# TPS65273V-Board.net
KiCad netlist of a schematic drawn in EAGLE
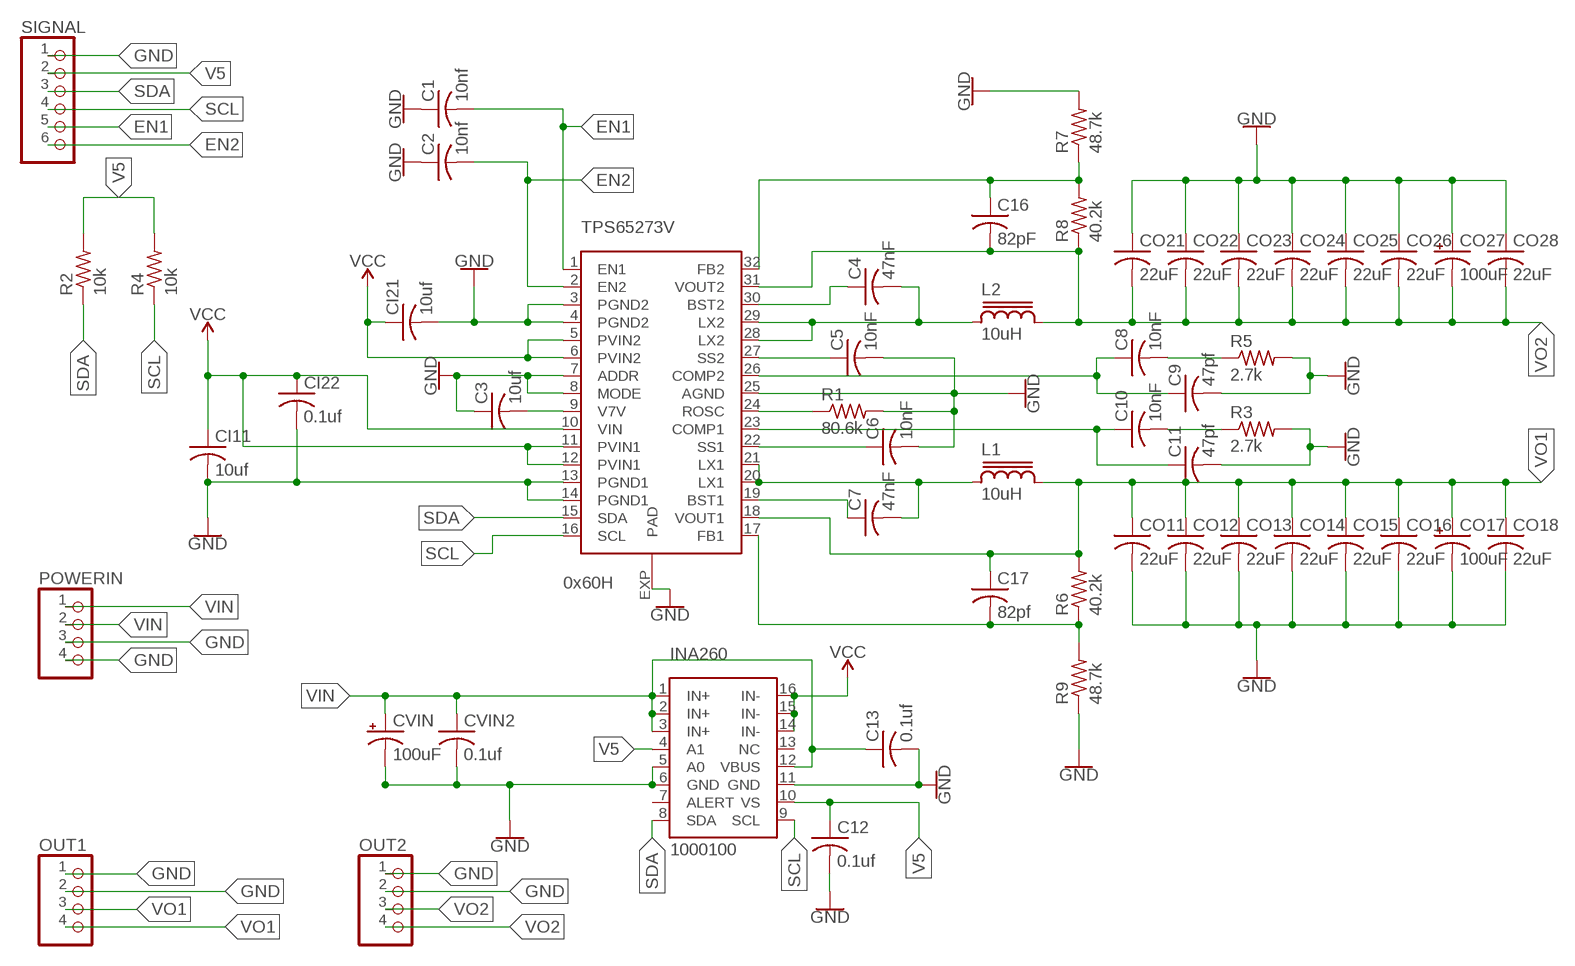
[diagram p0: schematic, sheet 1]

(export (version "E")
  (design (tool "Eeschema 10.0.6"))
  (components
    (comp (ref "C1")
      (value "10nf")
      (footprint "eagle-import:C0805")
      (libsource (lib "eagle-import") (part "C-USC0805"))
    )
    (comp (ref "C2")
      (value "10nf")
      (footprint "eagle-import:C0805")
      (libsource (lib "eagle-import") (part "C-USC0805"))
    )
    (comp (ref "C3")
      (value "10uf")
      (footprint "eagle-import:C0805")
      (libsource (lib "eagle-import") (part "C-USC0805"))
    )
    (comp (ref "C4")
      (value "47nF")
      (footprint "eagle-import:C0805")
      (libsource (lib "eagle-import") (part "C-USC0805"))
    )
    (comp (ref "C5")
      (value "10nF")
      (footprint "eagle-import:C0805")
      (libsource (lib "eagle-import") (part "C-USC0805"))
    )
    (comp (ref "C6")
      (value "10nF")
      (footprint "eagle-import:C0805")
      (libsource (lib "eagle-import") (part "C-USC0805"))
    )
    (comp (ref "C7")
      (value "47nF")
      (footprint "eagle-import:C0805")
      (libsource (lib "eagle-import") (part "C-USC0805"))
    )
    (comp (ref "C8")
      (value "10nF")
      (footprint "eagle-import:C0805")
      (libsource (lib "eagle-import") (part "C-USC0805"))
    )
    (comp (ref "C9")
      (value "47pf")
      (footprint "eagle-import:C0805")
      (libsource (lib "eagle-import") (part "C-USC0805"))
    )
    (comp (ref "C10")
      (value "10nF")
      (footprint "eagle-import:C0805")
      (libsource (lib "eagle-import") (part "C-USC0805"))
    )
    (comp (ref "C11")
      (value "47pf")
      (footprint "eagle-import:C0805")
      (libsource (lib "eagle-import") (part "C-USC0805"))
    )
    (comp (ref "C12")
      (value "0.1uf")
      (footprint "eagle-import:C0805")
      (libsource (lib "eagle-import") (part "C-USC0805"))
    )
    (comp (ref "C13")
      (value "0.1uf")
      (footprint "eagle-import:C0805")
      (libsource (lib "eagle-import") (part "C-USC0805"))
    )
    (comp (ref "C16")
      (value "82pF")
      (footprint "eagle-import:C0805")
      (libsource (lib "eagle-import") (part "C-USC0805"))
    )
    (comp (ref "C17")
      (value "82pf")
      (footprint "eagle-import:C0805")
      (libsource (lib "eagle-import") (part "C-USC0805"))
    )
    (comp (ref "CI11")
      (value "10uf")
      (footprint "eagle-import:C1210")
      (libsource (lib "eagle-import") (part "C-USC1210"))
    )
    (comp (ref "CI21")
      (value "10uf")
      (footprint "eagle-import:C1210")
      (libsource (lib "eagle-import") (part "C-USC1210"))
    )
    (comp (ref "CI22")
      (value "0.1uf")
      (footprint "eagle-import:C0805")
      (libsource (lib "eagle-import") (part "C-USC0805"))
    )
    (comp (ref "CO11")
      (value "22uF")
      (footprint "eagle-import:C0805")
      (libsource (lib "eagle-import") (part "C-USC0805"))
    )
    (comp (ref "CO12")
      (value "22uF")
      (footprint "eagle-import:C0805")
      (libsource (lib "eagle-import") (part "C-USC0805"))
    )
    (comp (ref "CO13")
      (value "22uF")
      (footprint "eagle-import:C0805")
      (libsource (lib "eagle-import") (part "C-USC0805"))
    )
    (comp (ref "CO14")
      (value "22uF")
      (footprint "eagle-import:C0805")
      (libsource (lib "eagle-import") (part "C-USC0805"))
    )
    (comp (ref "CO15")
      (value "22uF")
      (footprint "eagle-import:C0805")
      (libsource (lib "eagle-import") (part "C-USC0805"))
    )
    (comp (ref "CO16")
      (value "22uF")
      (footprint "eagle-import:C0805")
      (libsource (lib "eagle-import") (part "C-USC0805"))
    )
    (comp (ref "CO17")
      (value "100uF")
      (footprint "eagle-import:PANASONIC_D")
      (libsource (lib "eagle-import") (part "100UF-POLAR-25V-20%(ELEC)"))
    )
    (comp (ref "CO18")
      (value "22uF")
      (footprint "eagle-import:C0805")
      (libsource (lib "eagle-import") (part "C-USC0805"))
    )
    (comp (ref "CO21")
      (value "22uF")
      (footprint "eagle-import:C0805")
      (libsource (lib "eagle-import") (part "C-USC0805"))
    )
    (comp (ref "CO22")
      (value "22uF")
      (footprint "eagle-import:C0805")
      (libsource (lib "eagle-import") (part "C-USC0805"))
    )
    (comp (ref "CO23")
      (value "22uF")
      (footprint "eagle-import:C0805")
      (libsource (lib "eagle-import") (part "C-USC0805"))
    )
    (comp (ref "CO24")
      (value "22uF")
      (footprint "eagle-import:C0805")
      (libsource (lib "eagle-import") (part "C-USC0805"))
    )
    (comp (ref "CO25")
      (value "22uF")
      (footprint "eagle-import:C0805")
      (libsource (lib "eagle-import") (part "C-USC0805"))
    )
    (comp (ref "CO26")
      (value "22uF")
      (footprint "eagle-import:C0805")
      (libsource (lib "eagle-import") (part "C-USC0805"))
    )
    (comp (ref "CO27")
      (value "100uF")
      (footprint "eagle-import:PANASONIC_D")
      (libsource (lib "eagle-import") (part "100UF-POLAR-25V-20%(ELEC)"))
    )
    (comp (ref "CO28")
      (value "22uF")
      (footprint "eagle-import:C0805")
      (libsource (lib "eagle-import") (part "C-USC0805"))
    )
    (comp (ref "CVIN")
      (value "100uF")
      (footprint "eagle-import:PANASONIC_D")
      (libsource (lib "eagle-import") (part "100UF-POLAR-25V-20%(ELEC)"))
    )
    (comp (ref "CVIN2")
      (value "0.1uf")
      (footprint "eagle-import:C0805")
      (libsource (lib "eagle-import") (part "C-USC0805"))
    )
    (comp (ref "INA260")
      (value "1000100")
      (footprint "eagle-import:TSSOP16")
      (libsource (lib "eagle-import") (part "INA260"))
    )
    (comp (ref "L1")
      (value "10uH")
      (footprint "eagle-import:MSS1048")
      (libsource (lib "eagle-import") (part "MSS1048"))
    )
    (comp (ref "L2")
      (value "10uH")
      (footprint "eagle-import:MSS1048")
      (libsource (lib "eagle-import") (part "MSS1048"))
    )
    (comp (ref "OUT1")
      (value "PINHD-1X4")
      (footprint "eagle-import:1X04")
      (libsource (lib "eagle-import") (part "PINHD-1X4"))
    )
    (comp (ref "OUT2")
      (value "PINHD-1X4")
      (footprint "eagle-import:1X04")
      (libsource (lib "eagle-import") (part "PINHD-1X4"))
    )
    (comp (ref "POWERIN")
      (value "PINHD-1X4")
      (footprint "eagle-import:1X04")
      (libsource (lib "eagle-import") (part "PINHD-1X4"))
    )
    (comp (ref "R1")
      (value "80.6k")
      (footprint "eagle-import:R0805")
      (libsource (lib "eagle-import") (part "R-US_R0805"))
    )
    (comp (ref "R2")
      (value "10k")
      (footprint "eagle-import:R0805")
      (libsource (lib "eagle-import") (part "R-US_R0805"))
    )
    (comp (ref "R3")
      (value "2.7k")
      (footprint "eagle-import:R0805")
      (libsource (lib "eagle-import") (part "R-US_R0805"))
    )
    (comp (ref "R4")
      (value "10k")
      (footprint "eagle-import:R0805")
      (libsource (lib "eagle-import") (part "R-US_R0805"))
    )
    (comp (ref "R5")
      (value "2.7k")
      (footprint "eagle-import:R0805")
      (libsource (lib "eagle-import") (part "R-US_R0805"))
    )
    (comp (ref "R6")
      (value "40.2k")
      (footprint "eagle-import:R0805")
      (libsource (lib "eagle-import") (part "R-US_R0805"))
    )
    (comp (ref "R7")
      (value "48.7k")
      (footprint "eagle-import:R0805")
      (libsource (lib "eagle-import") (part "R-US_R0805"))
    )
    (comp (ref "R8")
      (value "40.2k")
      (footprint "eagle-import:R0805")
      (libsource (lib "eagle-import") (part "R-US_R0805"))
    )
    (comp (ref "R9")
      (value "48.7k")
      (footprint "eagle-import:R0805")
      (libsource (lib "eagle-import") (part "R-US_R0805"))
    )
    (comp (ref "SIGNAL")
      (value "PINHD-1X6")
      (footprint "eagle-import:1X06")
      (libsource (lib "eagle-import") (part "PINHD-1X6"))
    )
    (comp (ref "TPS65273V")
      (value "0x60H")
      (footprint "eagle-import:HTSSOP32DAP")
      (libsource (lib "eagle-import") (part "TPS65273V"))
    )
  )
  (nets
    (net (code "1") (name "EN1") (class "Default")
      (node (ref "C1") (pin "2") (pinfunction "2_2") (pintype "passive"))
      (node (ref "SIGNAL") (pin "5") (pinfunction "5_5") (pintype "passive"))
      (node (ref "TPS65273V") (pin "1") (pinfunction "EN1_1") (pintype "input"))
    )
    (net (code "2") (name "EN2") (class "Default")
      (node (ref "C2") (pin "2") (pinfunction "2_2") (pintype "passive"))
      (node (ref "SIGNAL") (pin "6") (pinfunction "6_6") (pintype "passive"))
      (node (ref "TPS65273V") (pin "2") (pinfunction "EN2_2") (pintype "input"))
    )
    (net (code "3") (name "GND") (class "Default")
      (node (ref "C1") (pin "1") (pinfunction "1_1") (pintype "passive"))
      (node (ref "C11") (pin "2") (pinfunction "2_2") (pintype "passive"))
      (node (ref "C12") (pin "2") (pinfunction "2_2") (pintype "passive"))
      (node (ref "C13") (pin "2") (pinfunction "2_2") (pintype "passive"))
      (node (ref "C2") (pin "1") (pinfunction "1_1") (pintype "passive"))
      (node (ref "C3") (pin "1") (pinfunction "1_1") (pintype "passive"))
      (node (ref "C5") (pin "2") (pinfunction "2_2") (pintype "passive"))
      (node (ref "C6") (pin "2") (pinfunction "2_2") (pintype "passive"))
      (node (ref "C9") (pin "2") (pinfunction "2_2") (pintype "passive"))
      (node (ref "CI11") (pin "2") (pinfunction "2_2") (pintype "passive"))
      (node (ref "CI21") (pin "2") (pinfunction "2_2") (pintype "passive"))
      (node (ref "CI22") (pin "2") (pinfunction "2_2") (pintype "passive"))
      (node (ref "CO11") (pin "2") (pinfunction "2_2") (pintype "passive"))
      (node (ref "CO12") (pin "2") (pinfunction "2_2") (pintype "passive"))
      (node (ref "CO13") (pin "2") (pinfunction "2_2") (pintype "passive"))
      (node (ref "CO14") (pin "2") (pinfunction "2_2") (pintype "passive"))
      (node (ref "CO15") (pin "2") (pinfunction "2_2") (pintype "passive"))
      (node (ref "CO16") (pin "2") (pinfunction "2_2") (pintype "passive"))
      (node (ref "CO17") (pin "-") (pinfunction "-_-") (pintype "passive"))
      (node (ref "CO18") (pin "2") (pinfunction "2_2") (pintype "passive"))
      (node (ref "CO21") (pin "1") (pinfunction "1_1") (pintype "passive"))
      (node (ref "CO22") (pin "1") (pinfunction "1_1") (pintype "passive"))
      (node (ref "CO23") (pin "1") (pinfunction "1_1") (pintype "passive"))
      (node (ref "CO24") (pin "1") (pinfunction "1_1") (pintype "passive"))
      (node (ref "CO25") (pin "1") (pinfunction "1_1") (pintype "passive"))
      (node (ref "CO26") (pin "1") (pinfunction "1_1") (pintype "passive"))
      (node (ref "CO27") (pin "+") (pinfunction "+_+") (pintype "passive"))
      (node (ref "CO28") (pin "1") (pinfunction "1_1") (pintype "passive"))
      (node (ref "CVIN") (pin "-") (pinfunction "-_-") (pintype "passive"))
      (node (ref "CVIN2") (pin "2") (pinfunction "2_2") (pintype "passive"))
      (node (ref "INA260") (pin "11") (pinfunction "GND_11") (pintype "power_in"))
      (node (ref "INA260") (pin "5") (pinfunction "A0_5") (pintype "input"))
      (node (ref "INA260") (pin "6") (pinfunction "GND_6") (pintype "power_in"))
      (node (ref "OUT1") (pin "1") (pinfunction "1_1") (pintype "passive"))
      (node (ref "OUT1") (pin "2") (pinfunction "2_2") (pintype "passive"))
      (node (ref "OUT2") (pin "1") (pinfunction "1_1") (pintype "passive"))
      (node (ref "OUT2") (pin "2") (pinfunction "2_2") (pintype "passive"))
      (node (ref "POWERIN") (pin "3") (pinfunction "3_3") (pintype "passive"))
      (node (ref "POWERIN") (pin "4") (pinfunction "4_4") (pintype "passive"))
      (node (ref "R1") (pin "2") (pinfunction "2_2") (pintype "passive"))
      (node (ref "R3") (pin "2") (pinfunction "2_2") (pintype "passive"))
      (node (ref "R5") (pin "2") (pinfunction "2_2") (pintype "passive"))
      (node (ref "R7") (pin "2") (pinfunction "2_2") (pintype "passive"))
      (node (ref "R9") (pin "1") (pinfunction "1_1") (pintype "passive"))
      (node (ref "SIGNAL") (pin "1") (pinfunction "1_1") (pintype "passive"))
      (node (ref "TPS65273V") (pin "13") (pinfunction "PGND1_13") (pintype "power_in"))
      (node (ref "TPS65273V") (pin "14") (pinfunction "PGND1_14") (pintype "power_in"))
      (node (ref "TPS65273V") (pin "25") (pinfunction "AGND_25") (pintype "power_in"))
      (node (ref "TPS65273V") (pin "3") (pinfunction "PGND2_3") (pintype "power_in"))
      (node (ref "TPS65273V") (pin "4") (pinfunction "PGND2_4") (pintype "power_in"))
      (node (ref "TPS65273V") (pin "7") (pinfunction "ADDR_7") (pintype "input"))
      (node (ref "TPS65273V") (pin "8") (pinfunction "MODE_8") (pintype "input"))
      (node (ref "TPS65273V") (pin "EXP") (pinfunction "PAD_EXP") (pintype "bidirectional"))
    )
    (net (code "4") (name "Net-(C4-Pad2)") (class "Default")
      (node (ref "C4") (pin "2") (pinfunction "2_2") (pintype "passive"))
      (node (ref "L2") (pin "1") (pinfunction "1_1") (pintype "passive"))
      (node (ref "TPS65273V") (pin "28") (pinfunction "LX2_28") (pintype "output"))
      (node (ref "TPS65273V") (pin "29") (pinfunction "LX2_29") (pintype "output"))
    )
    (net (code "5") (name "Net-(C7-Pad2)") (class "Default")
      (node (ref "C7") (pin "2") (pinfunction "2_2") (pintype "passive"))
      (node (ref "L1") (pin "1") (pinfunction "1_1") (pintype "passive"))
      (node (ref "TPS65273V") (pin "20") (pinfunction "LX1_20") (pintype "output"))
      (node (ref "TPS65273V") (pin "21") (pinfunction "LX1_21") (pintype "output"))
    )
    (net (code "6") (name "Net-(C8-Pad2)") (class "Default")
      (node (ref "C8") (pin "2") (pinfunction "2_2") (pintype "passive"))
      (node (ref "R5") (pin "1") (pinfunction "1_1") (pintype "passive"))
    )
    (net (code "7") (name "Net-(C10-Pad2)") (class "Default")
      (node (ref "C10") (pin "2") (pinfunction "2_2") (pintype "passive"))
      (node (ref "R3") (pin "1") (pinfunction "1_1") (pintype "passive"))
    )
    (net (code "8") (name "Net-(TPS65273V-BST1)") (class "Default")
      (node (ref "C7") (pin "1") (pinfunction "1_1") (pintype "passive"))
      (node (ref "TPS65273V") (pin "19") (pinfunction "BST1_19") (pintype "input"))
    )
    (net (code "9") (name "Net-(TPS65273V-BST2)") (class "Default")
      (node (ref "C4") (pin "1") (pinfunction "1_1") (pintype "passive"))
      (node (ref "TPS65273V") (pin "30") (pinfunction "BST2_30") (pintype "input"))
    )
    (net (code "10") (name "Net-(TPS65273V-COMP1)") (class "Default")
      (node (ref "C10") (pin "1") (pinfunction "1_1") (pintype "passive"))
      (node (ref "C11") (pin "1") (pinfunction "1_1") (pintype "passive"))
      (node (ref "TPS65273V") (pin "23") (pinfunction "COMP1_23") (pintype "input"))
    )
    (net (code "11") (name "Net-(TPS65273V-COMP2)") (class "Default")
      (node (ref "C8") (pin "1") (pinfunction "1_1") (pintype "passive"))
      (node (ref "C9") (pin "1") (pinfunction "1_1") (pintype "passive"))
      (node (ref "TPS65273V") (pin "26") (pinfunction "COMP2_26") (pintype "input"))
    )
    (net (code "12") (name "Net-(TPS65273V-FB1)") (class "Default")
      (node (ref "C17") (pin "2") (pinfunction "2_2") (pintype "passive"))
      (node (ref "R6") (pin "1") (pinfunction "1_1") (pintype "passive"))
      (node (ref "R9") (pin "2") (pinfunction "2_2") (pintype "passive"))
      (node (ref "TPS65273V") (pin "17") (pinfunction "FB1_17") (pintype "input"))
    )
    (net (code "13") (name "Net-(TPS65273V-FB2)") (class "Default")
      (node (ref "C16") (pin "1") (pinfunction "1_1") (pintype "passive"))
      (node (ref "R7") (pin "1") (pinfunction "1_1") (pintype "passive"))
      (node (ref "R8") (pin "2") (pinfunction "2_2") (pintype "passive"))
      (node (ref "TPS65273V") (pin "32") (pinfunction "FB2_32") (pintype "input"))
    )
    (net (code "14") (name "Net-(TPS65273V-ROSC)") (class "Default")
      (node (ref "R1") (pin "1") (pinfunction "1_1") (pintype "passive"))
      (node (ref "TPS65273V") (pin "24") (pinfunction "ROSC_24") (pintype "input"))
    )
    (net (code "15") (name "Net-(TPS65273V-SS1)") (class "Default")
      (node (ref "C6") (pin "1") (pinfunction "1_1") (pintype "passive"))
      (node (ref "TPS65273V") (pin "22") (pinfunction "SS1_22") (pintype "input"))
    )
    (net (code "16") (name "Net-(TPS65273V-SS2)") (class "Default")
      (node (ref "C5") (pin "1") (pinfunction "1_1") (pintype "passive"))
      (node (ref "TPS65273V") (pin "27") (pinfunction "SS2_27") (pintype "input"))
    )
    (net (code "17") (name "Net-(TPS65273V-V7V)") (class "Default")
      (node (ref "C3") (pin "2") (pinfunction "2_2") (pintype "passive"))
      (node (ref "TPS65273V") (pin "9") (pinfunction "V7V_9") (pintype "input"))
    )
    (net (code "18") (name "SCL") (class "Default")
      (node (ref "INA260") (pin "9") (pinfunction "SCL_9") (pintype "output"))
      (node (ref "R4") (pin "1") (pinfunction "1_1") (pintype "passive"))
      (node (ref "SIGNAL") (pin "4") (pinfunction "4_4") (pintype "passive"))
      (node (ref "TPS65273V") (pin "16") (pinfunction "SCL_16") (pintype "bidirectional"))
    )
    (net (code "19") (name "SDA") (class "Default")
      (node (ref "INA260") (pin "8") (pinfunction "SDA_8") (pintype "output"))
      (node (ref "R2") (pin "1") (pinfunction "1_1") (pintype "passive"))
      (node (ref "SIGNAL") (pin "3") (pinfunction "3_3") (pintype "passive"))
      (node (ref "TPS65273V") (pin "15") (pinfunction "SDA_15") (pintype "bidirectional"))
    )
    (net (code "20") (name "V5") (class "Default")
      (node (ref "C12") (pin "1") (pinfunction "1_1") (pintype "passive"))
      (node (ref "INA260") (pin "10") (pinfunction "VS_10") (pintype "power_in"))
      (node (ref "INA260") (pin "4") (pinfunction "A1_4") (pintype "input"))
      (node (ref "R2") (pin "2") (pinfunction "2_2") (pintype "passive"))
      (node (ref "R4") (pin "2") (pinfunction "2_2") (pintype "passive"))
      (node (ref "SIGNAL") (pin "2") (pinfunction "2_2") (pintype "passive"))
    )
    (net (code "21") (name "VCC") (class "Default")
      (node (ref "CI11") (pin "1") (pinfunction "1_1") (pintype "passive"))
      (node (ref "CI21") (pin "1") (pinfunction "1_1") (pintype "passive"))
      (node (ref "CI22") (pin "1") (pinfunction "1_1") (pintype "passive"))
      (node (ref "INA260") (pin "14") (pinfunction "IN-_14") (pintype "output"))
      (node (ref "INA260") (pin "15") (pinfunction "IN-_15") (pintype "output"))
      (node (ref "INA260") (pin "16") (pinfunction "IN-_16") (pintype "output"))
      (node (ref "TPS65273V") (pin "10") (pinfunction "VIN_10") (pintype "power_in"))
      (node (ref "TPS65273V") (pin "11") (pinfunction "PVIN1_11") (pintype "power_in"))
      (node (ref "TPS65273V") (pin "12") (pinfunction "PVIN1_12") (pintype "power_in"))
      (node (ref "TPS65273V") (pin "5") (pinfunction "PVIN2_5") (pintype "power_in"))
      (node (ref "TPS65273V") (pin "6") (pinfunction "PVIN2_6") (pintype "power_in"))
    )
    (net (code "22") (name "VIN") (class "Default")
      (node (ref "C13") (pin "1") (pinfunction "1_1") (pintype "passive"))
      (node (ref "CVIN") (pin "+") (pinfunction "+_+") (pintype "passive"))
      (node (ref "CVIN2") (pin "1") (pinfunction "1_1") (pintype "passive"))
      (node (ref "INA260") (pin "1") (pinfunction "IN+_1") (pintype "input"))
      (node (ref "INA260") (pin "12") (pinfunction "VBUS_12") (pintype "power_in"))
      (node (ref "INA260") (pin "2") (pinfunction "IN+_2") (pintype "input"))
      (node (ref "INA260") (pin "3") (pinfunction "IN+_3") (pintype "input"))
      (node (ref "POWERIN") (pin "1") (pinfunction "1_1") (pintype "passive"))
      (node (ref "POWERIN") (pin "2") (pinfunction "2_2") (pintype "passive"))
    )
    (net (code "23") (name "VO1") (class "Default")
      (node (ref "C17") (pin "1") (pinfunction "1_1") (pintype "passive"))
      (node (ref "CO11") (pin "1") (pinfunction "1_1") (pintype "passive"))
      (node (ref "CO12") (pin "1") (pinfunction "1_1") (pintype "passive"))
      (node (ref "CO13") (pin "1") (pinfunction "1_1") (pintype "passive"))
      (node (ref "CO14") (pin "1") (pinfunction "1_1") (pintype "passive"))
      (node (ref "CO15") (pin "1") (pinfunction "1_1") (pintype "passive"))
      (node (ref "CO16") (pin "1") (pinfunction "1_1") (pintype "passive"))
      (node (ref "CO17") (pin "+") (pinfunction "+_+") (pintype "passive"))
      (node (ref "CO18") (pin "1") (pinfunction "1_1") (pintype "passive"))
      (node (ref "L1") (pin "2") (pinfunction "2_2") (pintype "passive"))
      (node (ref "OUT1") (pin "3") (pinfunction "3_3") (pintype "passive"))
      (node (ref "OUT1") (pin "4") (pinfunction "4_4") (pintype "passive"))
      (node (ref "R6") (pin "2") (pinfunction "2_2") (pintype "passive"))
      (node (ref "TPS65273V") (pin "18") (pinfunction "VOUT1_18") (pintype "input"))
    )
    (net (code "24") (name "VO2") (class "Default")
      (node (ref "C16") (pin "2") (pinfunction "2_2") (pintype "passive"))
      (node (ref "CO21") (pin "2") (pinfunction "2_2") (pintype "passive"))
      (node (ref "CO22") (pin "2") (pinfunction "2_2") (pintype "passive"))
      (node (ref "CO23") (pin "2") (pinfunction "2_2") (pintype "passive"))
      (node (ref "CO24") (pin "2") (pinfunction "2_2") (pintype "passive"))
      (node (ref "CO25") (pin "2") (pinfunction "2_2") (pintype "passive"))
      (node (ref "CO26") (pin "2") (pinfunction "2_2") (pintype "passive"))
      (node (ref "CO27") (pin "-") (pinfunction "-_-") (pintype "passive"))
      (node (ref "CO28") (pin "2") (pinfunction "2_2") (pintype "passive"))
      (node (ref "L2") (pin "2") (pinfunction "2_2") (pintype "passive"))
      (node (ref "OUT2") (pin "3") (pinfunction "3_3") (pintype "passive"))
      (node (ref "OUT2") (pin "4") (pinfunction "4_4") (pintype "passive"))
      (node (ref "R8") (pin "1") (pinfunction "1_1") (pintype "passive"))
      (node (ref "TPS65273V") (pin "31") (pinfunction "VOUT2_31") (pintype "input"))
    )
    (net (code "25") (name "unconnected-(INA260-ALERT-Pad7)") (class "Default")
      (node (ref "INA260") (pin "7") (pinfunction "ALERT_7") (pintype "output"))
    )
    (net (code "26") (name "unconnected-(INA260-NC-Pad13)") (class "Default")
      (node (ref "INA260") (pin "13") (pinfunction "NC_13") (pintype "no_connect"))
    )
  )
)
